# 6_STM32F103.net
KiCad netlist of a schematic drawn in Altium Designer
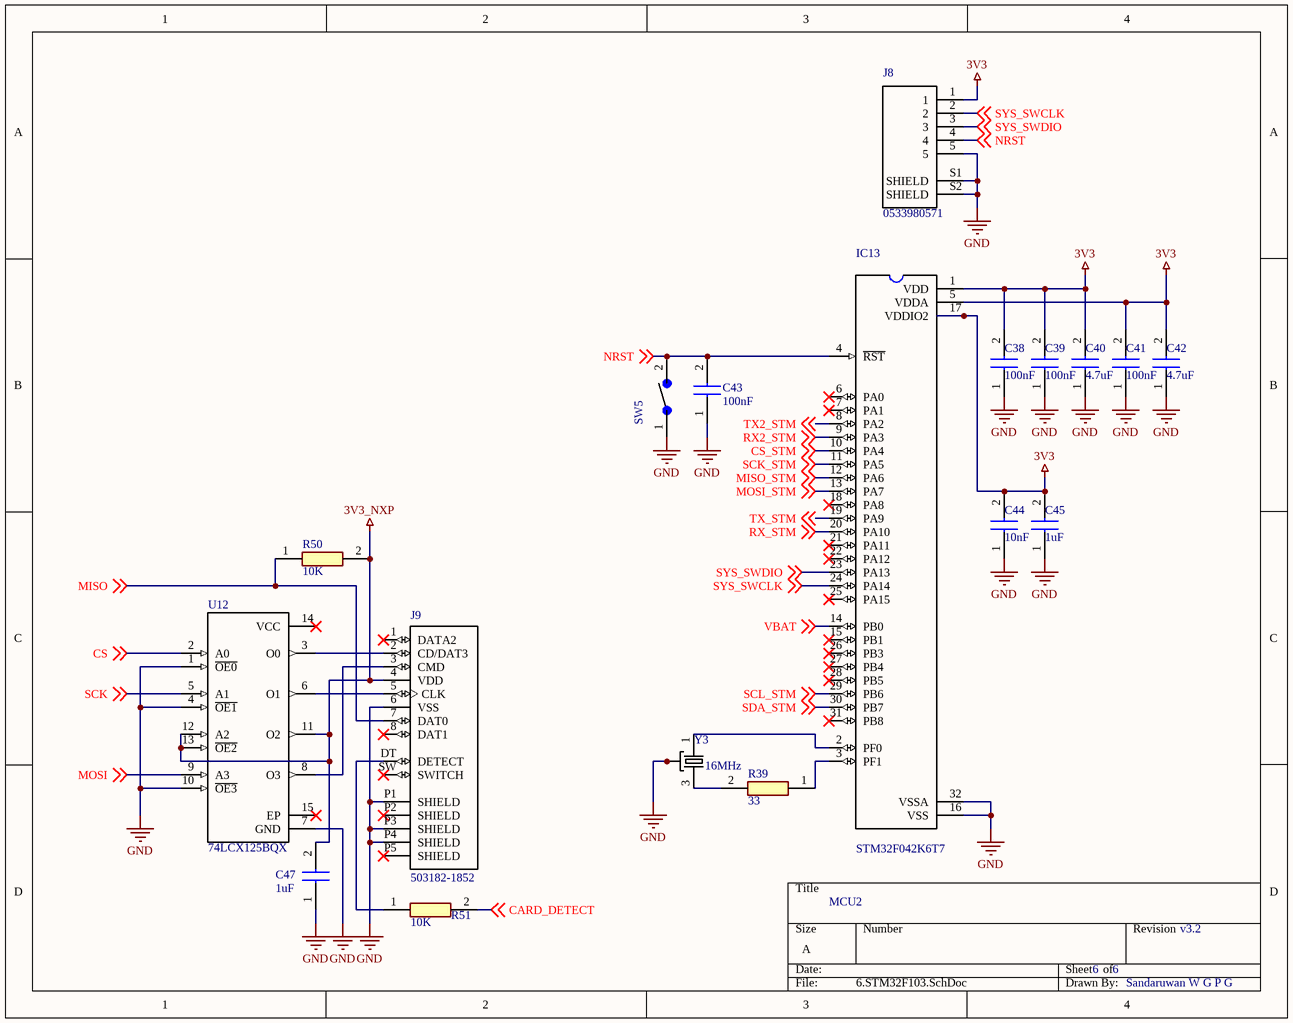
[diagram p0: 6.STM32F103.SchDoc]

(export (version "E")
  (design (tool "Eeschema 10.0.6"))
  (components
    (comp (ref "C38")
      (value "100nF")
      (footprint "*CAPC1608X95N")
      (description "Capacitor")
      (fields (field (name "Comment") "capacitor 0603"))
      (libsource (lib "micromouse library") (part "capacitor 0603"))
    )
    (comp (ref "C39")
      (value "100nF")
      (footprint "*CAPC1608X95N")
      (description "Capacitor")
      (fields (field (name "Comment") "capacitor 0603"))
      (libsource (lib "micromouse library") (part "capacitor 0603"))
    )
    (comp (ref "C40")
      (value "4.7uF")
      (footprint "*CAPC1608X95N")
      (description "Capacitor")
      (fields (field (name "Comment") "capacitor 0603"))
      (libsource (lib "micromouse library") (part "capacitor 0603"))
    )
    (comp (ref "C41")
      (value "100nF")
      (footprint "*CAPC1608X95N")
      (description "Capacitor")
      (fields (field (name "Comment") "capacitor 0603"))
      (libsource (lib "micromouse library") (part "capacitor 0603"))
    )
    (comp (ref "C42")
      (value "4.7uF")
      (footprint "*CAPC1608X95N")
      (description "Capacitor")
      (fields (field (name "Comment") "capacitor 0603"))
      (libsource (lib "micromouse library") (part "capacitor 0603"))
    )
    (comp (ref "C43")
      (value "100nF")
      (footprint "*CAPC1608X95N")
      (description "Capacitor")
      (fields (field (name "Comment") "capacitor 0603"))
      (libsource (lib "micromouse library") (part "capacitor 0603"))
    )
    (comp (ref "C44")
      (value "10nF")
      (footprint "*CAPC1608X95N")
      (description "Capacitor")
      (fields (field (name "Comment") "capacitor 0603"))
      (libsource (lib "micromouse library") (part "capacitor 0603"))
    )
    (comp (ref "C45")
      (value "1uF")
      (footprint "*CAPC1608X95N")
      (description "Capacitor")
      (fields (field (name "Comment") "capacitor 0603"))
      (libsource (lib "micromouse library") (part "capacitor 0603"))
    )
    (comp (ref "C47")
      (value "1uF")
      (footprint "*CAPC1608X95N")
      (description "Capacitor")
      (fields (field (name "Comment") "capacitor 0603"))
      (libsource (lib "micromouse library") (part "capacitor 0603"))
    )
    (comp (ref "IC13")
      (value "STM32F042K6T7")
      (footprint "*QFP80P900X900X160-32N")
      (fields (field (name "MF") "STMicroelectronics"))
      (libsource (lib "micromouse library") (part "STM32F042K6T7"))
    )
    (comp (ref "J8")
      (value "0533980571")
      (footprint "*MOLEX_0533980571_0533980571(Primary)")
      (description "Conn Shrouded Header HDR 5 POS 1.25mm Solder ST SMD PicoBladeÃƒÂ¢Ã¢Â€ÂžÂ¢ Embossed T/R")
      (fields (field (name "MF") "Molex"))
      (libsource (lib "micromouse library") (part "0533980571"))
    )
    (comp (ref "J9")
      (value "503182-1852")
      (footprint "*MOLEX_503182-1852_503182-1852(Primary)")
      (description "MICRO SD NORMAL ULTRALOWPRO8CKTE")
      (fields (field (name "MF") "Molex") (field (name "MP") "5031821852"))
      (libsource (lib "micromouse library") (part "503182-1852"))
    )
    (comp (ref "R39")
      (value "33")
      (footprint "RESC1608X55N")
      (description "Resistor")
      (fields (field (name "Comment") "resistor"))
      (libsource (lib "micromouse library") (part "resistor"))
    )
    (comp (ref "R50")
      (value "10K")
      (footprint "RESC1608X55N")
      (description "Resistor")
      (fields (field (name "Comment") "resistor"))
      (libsource (lib "") (part "resistor_1"))
    )
    (comp (ref "R51")
      (value "10K")
      (footprint "RESC1608X55N")
      (description "Resistor")
      (fields (field (name "Comment") "resistor"))
      (libsource (lib "") (part "resistor_1"))
    )
    (comp (ref "SW5")
      (value "1437566-3")
      (footprint "*TE_FSMSM")
      (description "Switch Tactile OFF _ON_ SPST Rectangular Button Gull Wing 0.05A 12VDC SMD Loose Piece")
      (fields (field (name "MF") "TE Connectivity") (field (name "MP") "FSMSM"))
      (libsource (lib "micromouse library") (part "FSMSM"))
    )
    (comp (ref "U12")
      (value "74LCX125BQX")
      (footprint "*QFN50P300X250X85-15N")
      (description "Buffer/Line Driver 4-CH Non-Inverting 3-ST CMOS 14-Pin DQFN EP T/R")
      (fields (field (name "MF") "ON Semiconductor"))
      (libsource (lib "micromouse library") (part "74LCX125BQX"))
    )
    (comp (ref "Y3")
      (value "16MHz")
      (footprint "*OSCCC320X250X60N")
      (description "Crystal 12.0000mhz 8pf Smd")
      (fields (field (name "MP") "NX3225SA-12.000M-STD-CRS-2") (field (name "MF") "NDK America,"))
      (libsource (lib "micromouse library") (part "NX3225SA-12.000M-STD-CRS-2"))
    )
  )
  (nets
    (net (code "1") (name "3V3") (class "Default")
      (node (ref "C38") (pin "2") (pinfunction "2_2") (pintype "passive"))
      (node (ref "C39") (pin "2") (pinfunction "2_2") (pintype "passive"))
      (node (ref "C40") (pin "2") (pinfunction "2_2") (pintype "passive"))
      (node (ref "C41") (pin "2") (pinfunction "2_2") (pintype "passive"))
      (node (ref "C42") (pin "2") (pinfunction "2_2") (pintype "passive"))
      (node (ref "C44") (pin "2") (pinfunction "2_2") (pintype "passive"))
      (node (ref "C45") (pin "2") (pinfunction "2_2") (pintype "passive"))
      (node (ref "IC13") (pin "1") (pinfunction "VDD_1") (pintype "power_in"))
      (node (ref "IC13") (pin "17") (pinfunction "VDDIO2_17") (pintype "power_in"))
      (node (ref "IC13") (pin "5") (pinfunction "VDDA_5") (pintype "power_in"))
      (node (ref "J8") (pin "1") (pinfunction "1_1") (pintype "passive"))
    )
    (net (code "2") (name "3V3_NXP") (class "Default")
      (node (ref "C47") (pin "2") (pinfunction "2_2") (pintype "passive"))
      (node (ref "J9") (pin "4") (pinfunction "VDD_4") (pintype "power_in"))
      (node (ref "R50") (pin "2") (pinfunction "2_2") (pintype "passive"))
      (node (ref "U12") (pin "11") (pinfunction "O2_11") (pintype "output"))
      (node (ref "U12") (pin "12") (pinfunction "A2_12") (pintype "input"))
      (node (ref "U12") (pin "13") (pinfunction "~{OE2}_13") (pintype "input"))
    )
    (net (code "3") (name "CARD_DETECT") (class "Default")
      (node (ref "R51") (pin "2") (pinfunction "2_2") (pintype "passive"))
    )
    (net (code "4") (name "CS") (class "Default")
      (node (ref "U12") (pin "2") (pinfunction "A0_2") (pintype "input"))
    )
    (net (code "5") (name "CS_STM") (class "Default")
      (node (ref "IC13") (pin "10") (pinfunction "PA4_10") (pintype "bidirectional"))
    )
    (net (code "6") (name "GND") (class "Default")
      (node (ref "C38") (pin "1") (pinfunction "1_1") (pintype "passive"))
      (node (ref "C39") (pin "1") (pinfunction "1_1") (pintype "passive"))
      (node (ref "C40") (pin "1") (pinfunction "1_1") (pintype "passive"))
      (node (ref "C41") (pin "1") (pinfunction "1_1") (pintype "passive"))
      (node (ref "C42") (pin "1") (pinfunction "1_1") (pintype "passive"))
      (node (ref "C43") (pin "1") (pinfunction "1_1") (pintype "passive"))
      (node (ref "C44") (pin "1") (pinfunction "1_1") (pintype "passive"))
      (node (ref "C45") (pin "1") (pinfunction "1_1") (pintype "passive"))
      (node (ref "C47") (pin "1") (pinfunction "1_1") (pintype "passive"))
      (node (ref "IC13") (pin "16") (pinfunction "VSS_16") (pintype "passive"))
      (node (ref "IC13") (pin "32") (pinfunction "VSSA_32") (pintype "passive"))
      (node (ref "J8") (pin "5") (pinfunction "5_5") (pintype "passive"))
      (node (ref "J8") (pin "S1") (pinfunction "SHIELD_S1") (pintype "passive"))
      (node (ref "J8") (pin "S2") (pinfunction "SHIELD_S2") (pintype "passive"))
      (node (ref "J9") (pin "6") (pinfunction "VSS_6") (pintype "power_in"))
      (node (ref "J9") (pin "P1") (pinfunction "SHIELD_P1") (pintype "passive"))
      (node (ref "J9") (pin "P3") (pinfunction "SHIELD_P3") (pintype "passive"))
      (node (ref "J9") (pin "P4") (pinfunction "SHIELD_P4") (pintype "passive"))
      (node (ref "SW5") (pin "1") (pinfunction "1_1") (pintype "passive"))
      (node (ref "U12") (pin "1") (pinfunction "~{OE0}_1") (pintype "input"))
      (node (ref "U12") (pin "10") (pinfunction "~{OE3}_10") (pintype "input"))
      (node (ref "U12") (pin "4") (pinfunction "~{OE1}_4") (pintype "input"))
      (node (ref "U12") (pin "7") (pinfunction "GND_7") (pintype "power_in"))
      (node (ref "Y3") (pin "2") (pinfunction "GND_2") (pintype "passive"))
      (node (ref "Y3") (pin "4") (pinfunction "GND_4") (pintype "passive"))
    )
    (net (code "7") (name "MISO") (class "Default")
      (node (ref "J9") (pin "7") (pinfunction "DAT0_7") (pintype "bidirectional"))
      (node (ref "R50") (pin "1") (pinfunction "1_1") (pintype "passive"))
    )
    (net (code "8") (name "MISO_STM") (class "Default")
      (node (ref "IC13") (pin "12") (pinfunction "PA6_12") (pintype "bidirectional"))
    )
    (net (code "9") (name "MOSI") (class "Default")
      (node (ref "U12") (pin "9") (pinfunction "A3_9") (pintype "input"))
    )
    (net (code "10") (name "MOSI_STM") (class "Default")
      (node (ref "IC13") (pin "13") (pinfunction "PA7_13") (pintype "bidirectional"))
    )
    (net (code "11") (name "NRST") (class "Default")
      (node (ref "C43") (pin "2") (pinfunction "2_2") (pintype "passive"))
      (node (ref "IC13") (pin "4") (pinfunction "~{RST}_4") (pintype "input"))
      (node (ref "J8") (pin "4") (pinfunction "4_4") (pintype "passive"))
      (node (ref "SW5") (pin "2") (pinfunction "2_2") (pintype "passive"))
    )
    (net (code "12") (name "Net-(IC13-PF0)") (class "Default")
      (node (ref "IC13") (pin "2") (pinfunction "PF0_2") (pintype "bidirectional"))
      (node (ref "Y3") (pin "1") (pinfunction "1_1") (pintype "passive"))
    )
    (net (code "13") (name "Net-(IC13-PF1)") (class "Default")
      (node (ref "IC13") (pin "3") (pinfunction "PF1_3") (pintype "bidirectional"))
      (node (ref "R39") (pin "1") (pinfunction "1_1") (pintype "passive"))
    )
    (net (code "14") (name "Net-(J9-CD{slash}DAT3)") (class "Default")
      (node (ref "J9") (pin "2") (pinfunction "CD/DAT3_2") (pintype "bidirectional"))
      (node (ref "U12") (pin "3") (pinfunction "O0_3") (pintype "output"))
    )
    (net (code "15") (name "Net-(J9-CLK)") (class "Default")
      (node (ref "J9") (pin "5") (pinfunction "CLK_5") (pintype "bidirectional"))
      (node (ref "U12") (pin "6") (pinfunction "O1_6") (pintype "output"))
    )
    (net (code "16") (name "Net-(J9-CMD)") (class "Default")
      (node (ref "J9") (pin "3") (pinfunction "CMD_3") (pintype "bidirectional"))
      (node (ref "U12") (pin "8") (pinfunction "O3_8") (pintype "output"))
    )
    (net (code "17") (name "Net-(J9-DETECT)") (class "Default")
      (node (ref "J9") (pin "DT") (pinfunction "DETECT_DT") (pintype "bidirectional"))
      (node (ref "R51") (pin "1") (pinfunction "1_1") (pintype "passive"))
    )
    (net (code "18") (name "Net-(R39-Pad2)") (class "Default")
      (node (ref "R39") (pin "2") (pinfunction "2_2") (pintype "passive"))
      (node (ref "Y3") (pin "3") (pinfunction "3_3") (pintype "passive"))
    )
    (net (code "19") (name "RX2_STM") (class "Default")
      (node (ref "IC13") (pin "9") (pinfunction "PA3_9") (pintype "bidirectional"))
    )
    (net (code "20") (name "RX_STM") (class "Default")
      (node (ref "IC13") (pin "20") (pinfunction "PA10_20") (pintype "bidirectional"))
    )
    (net (code "21") (name "SCK") (class "Default")
      (node (ref "U12") (pin "5") (pinfunction "A1_5") (pintype "input"))
    )
    (net (code "22") (name "SCK_STM") (class "Default")
      (node (ref "IC13") (pin "11") (pinfunction "PA5_11") (pintype "bidirectional"))
    )
    (net (code "23") (name "SCL_STM") (class "Default")
      (node (ref "IC13") (pin "29") (pinfunction "PB6_29") (pintype "bidirectional"))
    )
    (net (code "24") (name "SDA_STM") (class "Default")
      (node (ref "IC13") (pin "30") (pinfunction "PB7_30") (pintype "bidirectional"))
    )
    (net (code "25") (name "SYS_SWCLK") (class "Default")
      (node (ref "IC13") (pin "24") (pinfunction "PA14_24") (pintype "bidirectional"))
      (node (ref "J8") (pin "2") (pinfunction "2_2") (pintype "passive"))
    )
    (net (code "26") (name "SYS_SWDIO") (class "Default")
      (node (ref "IC13") (pin "23") (pinfunction "PA13_23") (pintype "bidirectional"))
      (node (ref "J8") (pin "3") (pinfunction "3_3") (pintype "passive"))
    )
    (net (code "27") (name "TX2_STM") (class "Default")
      (node (ref "IC13") (pin "8") (pinfunction "PA2_8") (pintype "bidirectional"))
    )
    (net (code "28") (name "TX_STM") (class "Default")
      (node (ref "IC13") (pin "19") (pinfunction "PA9_19") (pintype "bidirectional"))
    )
    (net (code "29") (name "VBAT") (class "Default")
      (node (ref "IC13") (pin "14") (pinfunction "PB0_14") (pintype "bidirectional"))
    )
    (net (code "30") (name "unconnected-(IC13-PA0-Pad6)") (class "Default")
      (node (ref "IC13") (pin "6") (pinfunction "PA0_6") (pintype "bidirectional+no_connect"))
    )
    (net (code "31") (name "unconnected-(IC13-PA1-Pad7)") (class "Default")
      (node (ref "IC13") (pin "7") (pinfunction "PA1_7") (pintype "bidirectional+no_connect"))
    )
    (net (code "32") (name "unconnected-(IC13-PA8-Pad18)") (class "Default")
      (node (ref "IC13") (pin "18") (pinfunction "PA8_18") (pintype "bidirectional+no_connect"))
    )
    (net (code "33") (name "unconnected-(IC13-PA11-Pad21)") (class "Default")
      (node (ref "IC13") (pin "21") (pinfunction "PA11_21") (pintype "bidirectional+no_connect"))
    )
    (net (code "34") (name "unconnected-(IC13-PA12-Pad22)") (class "Default")
      (node (ref "IC13") (pin "22") (pinfunction "PA12_22") (pintype "bidirectional+no_connect"))
    )
    (net (code "35") (name "unconnected-(IC13-PA15-Pad25)") (class "Default")
      (node (ref "IC13") (pin "25") (pinfunction "PA15_25") (pintype "bidirectional+no_connect"))
    )
    (net (code "36") (name "unconnected-(IC13-PB1-Pad15)") (class "Default")
      (node (ref "IC13") (pin "15") (pinfunction "PB1_15") (pintype "bidirectional+no_connect"))
    )
    (net (code "37") (name "unconnected-(IC13-PB3-Pad26)") (class "Default")
      (node (ref "IC13") (pin "26") (pinfunction "PB3_26") (pintype "bidirectional+no_connect"))
    )
    (net (code "38") (name "unconnected-(IC13-PB4-Pad27)") (class "Default")
      (node (ref "IC13") (pin "27") (pinfunction "PB4_27") (pintype "bidirectional+no_connect"))
    )
    (net (code "39") (name "unconnected-(IC13-PB5-Pad28)") (class "Default")
      (node (ref "IC13") (pin "28") (pinfunction "PB5_28") (pintype "bidirectional+no_connect"))
    )
    (net (code "40") (name "unconnected-(IC13-PB8-Pad31)") (class "Default")
      (node (ref "IC13") (pin "31") (pinfunction "PB8_31") (pintype "bidirectional+no_connect"))
    )
    (net (code "41") (name "unconnected-(J9-DAT1-Pad8)") (class "Default")
      (node (ref "J9") (pin "8") (pinfunction "DAT1_8") (pintype "bidirectional+no_connect"))
    )
    (net (code "42") (name "unconnected-(J9-DATA2-Pad1)") (class "Default")
      (node (ref "J9") (pin "1") (pinfunction "DATA2_1") (pintype "bidirectional+no_connect"))
    )
    (net (code "43") (name "unconnected-(J9-SHIELD-PadP2)") (class "Default")
      (node (ref "J9") (pin "P2") (pinfunction "SHIELD_P2") (pintype "passive+no_connect"))
    )
    (net (code "44") (name "unconnected-(J9-SHIELD-PadP5)") (class "Default")
      (node (ref "J9") (pin "P5") (pinfunction "SHIELD_P5") (pintype "passive+no_connect"))
    )
    (net (code "45") (name "unconnected-(J9-SWITCH-PadSW)") (class "Default")
      (node (ref "J9") (pin "SW") (pinfunction "SWITCH_SW") (pintype "bidirectional+no_connect"))
    )
    (net (code "46") (name "unconnected-(U12-EP-Pad15)") (class "Default")
      (node (ref "U12") (pin "15") (pinfunction "EP_15") (pintype "power_in+no_connect"))
    )
    (net (code "47") (name "unconnected-(U12-VCC-Pad14)") (class "Default")
      (node (ref "U12") (pin "14") (pinfunction "VCC_14") (pintype "power_in+no_connect"))
    )
  )
)
